# design.net
KiCad netlist of a schematic drawn in EasyEDA Pro
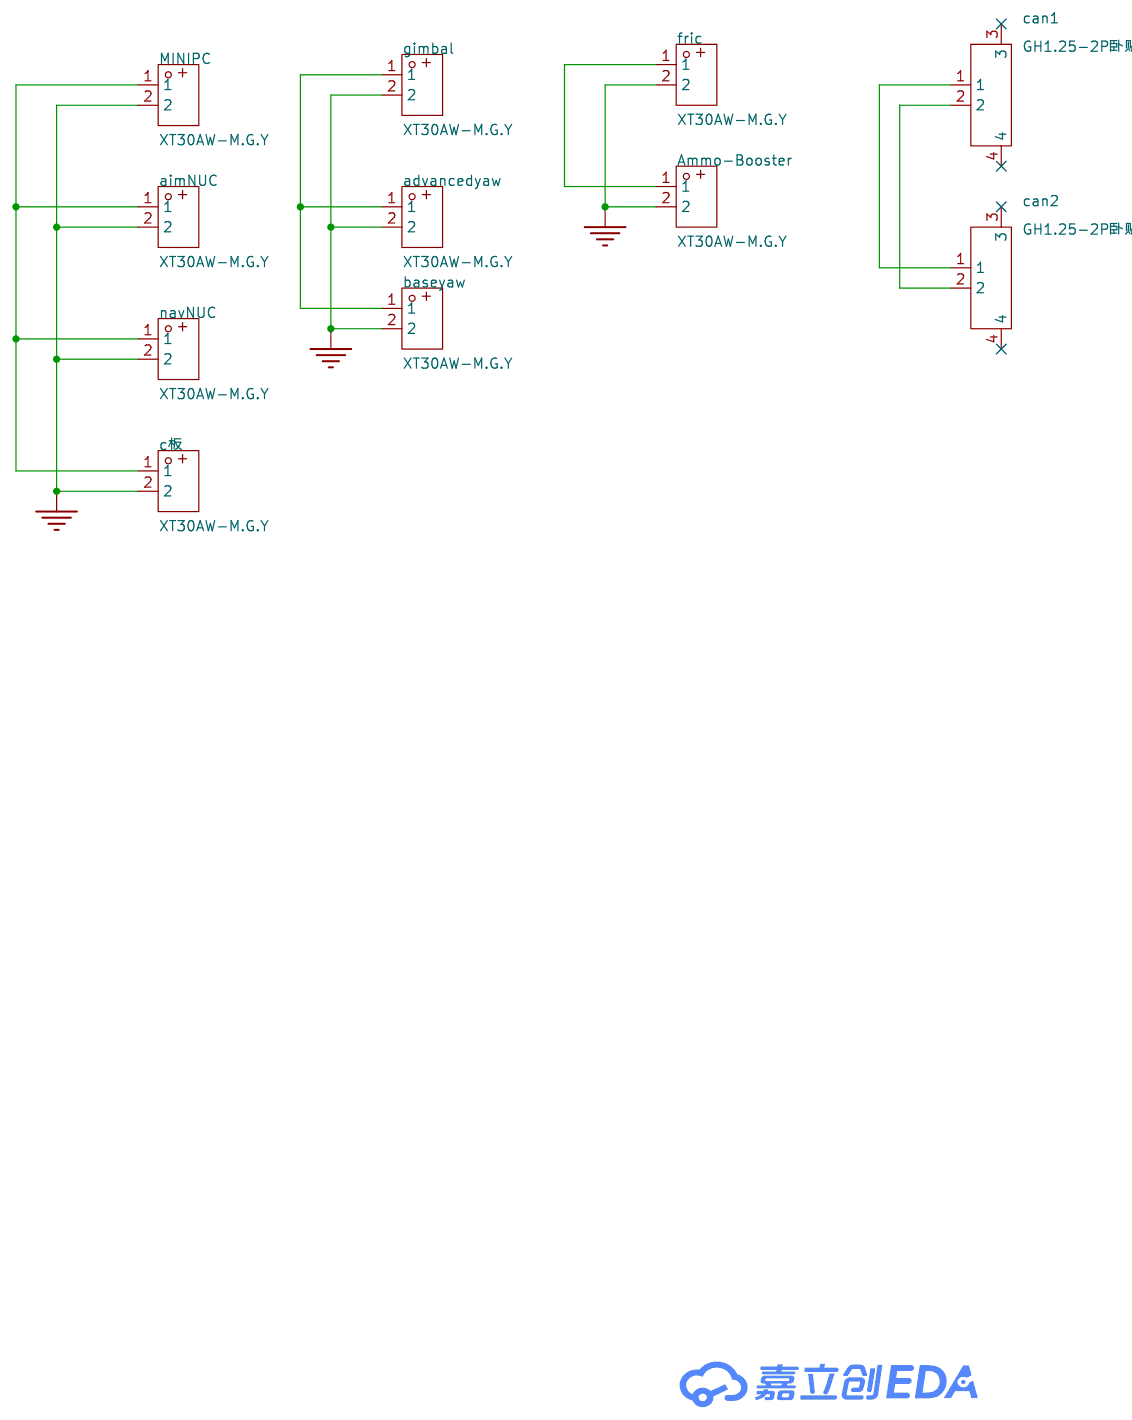
[diagram p0: schematic sheet]

(export (version "E")
  (design (tool "Eeschema 10.0.6"))
  (components
    (comp (ref "advancedyaw")
      (value "XT30AW-M.G.Y")
      (footprint "easyedapro:CONN-TH_XT30AW-M.G.Y")
      (fields (field (name "Manufacturer") "AMASS(艾迈斯)"))
      (libsource (lib "easyedapro") (part "XT30AW-M.G.Y"))
    )
    (comp (ref "aimNUC")
      (value "XT30AW-M.G.Y")
      (footprint "easyedapro:CONN-TH_XT30AW-M.G.Y")
      (fields (field (name "Manufacturer") "AMASS(艾迈斯)"))
      (libsource (lib "easyedapro") (part "XT30AW-M.G.Y"))
    )
    (comp (ref "Ammo-Booster")
      (value "XT30AW-M.G.Y")
      (footprint "easyedapro:CONN-TH_XT30AW-M.G.Y")
      (fields (field (name "Manufacturer") "AMASS(艾迈斯)"))
      (libsource (lib "easyedapro") (part "XT30AW-M.G.Y"))
    )
    (comp (ref "baseyaw")
      (value "XT30AW-M.G.Y")
      (footprint "easyedapro:CONN-TH_XT30AW-M.G.Y")
      (fields (field (name "Manufacturer") "AMASS(艾迈斯)"))
      (libsource (lib "easyedapro") (part "XT30AW-M.G.Y"))
    )
    (comp (ref "can1")
      (value "GH1.25-2P卧贴")
      (footprint "easyedapro:CONN-SMD_2P-P1.25_X1251WRS-02HF-LPSW")
      (libsource (lib "easyedapro") (part "GH1.25-2P卧贴_C9900015099"))
    )
    (comp (ref "can2")
      (value "GH1.25-2P卧贴")
      (footprint "easyedapro:CONN-SMD_2P-P1.25_X1251WRS-02HF-LPSW")
      (libsource (lib "easyedapro") (part "GH1.25-2P卧贴_C9900015099"))
    )
    (comp (ref "c板")
      (value "XT30AW-M.G.Y")
      (footprint "easyedapro:CONN-TH_XT30AW-M.G.Y")
      (fields (field (name "Manufacturer") "AMASS(艾迈斯)"))
      (libsource (lib "easyedapro") (part "XT30AW-M.G.Y"))
    )
    (comp (ref "fric")
      (value "XT30AW-M.G.Y")
      (footprint "easyedapro:CONN-TH_XT30AW-M.G.Y")
      (fields (field (name "Manufacturer") "AMASS(艾迈斯)"))
      (libsource (lib "easyedapro") (part "XT30AW-M.G.Y"))
    )
    (comp (ref "gimbal")
      (value "XT30AW-M.G.Y")
      (footprint "easyedapro:CONN-TH_XT30AW-M.G.Y")
      (fields (field (name "Manufacturer") "AMASS(艾迈斯)"))
      (libsource (lib "easyedapro") (part "XT30AW-M.G.Y"))
    )
    (comp (ref "MINIPC")
      (value "XT30AW-M.G.Y")
      (footprint "easyedapro:CONN-TH_XT30AW-M.G.Y")
      (fields (field (name "Manufacturer") "AMASS(艾迈斯)"))
      (libsource (lib "easyedapro") (part "XT30AW-M.G.Y"))
    )
    (comp (ref "navNUC")
      (value "XT30AW-M.G.Y")
      (footprint "easyedapro:CONN-TH_XT30AW-M.G.Y")
      (fields (field (name "Manufacturer") "AMASS(艾迈斯)"))
      (libsource (lib "easyedapro") (part "XT30AW-M.G.Y"))
    )
  )
  (nets
    (net (code "1") (name "GND") (class "Default")
      (node (ref "Ammo-Booster") (pin "2") (pinfunction "2_2") (pintype "unspecified"))
      (node (ref "MINIPC") (pin "2") (pinfunction "2_2") (pintype "unspecified"))
      (node (ref "advancedyaw") (pin "2") (pinfunction "2_2") (pintype "unspecified"))
      (node (ref "aimNUC") (pin "2") (pinfunction "2_2") (pintype "unspecified"))
      (node (ref "baseyaw") (pin "2") (pinfunction "2_2") (pintype "unspecified"))
      (node (ref "c板") (pin "2") (pinfunction "2_2") (pintype "unspecified"))
      (node (ref "fric") (pin "2") (pinfunction "2_2") (pintype "unspecified"))
      (node (ref "gimbal") (pin "2") (pinfunction "2_2") (pintype "unspecified"))
      (node (ref "navNUC") (pin "2") (pinfunction "2_2") (pintype "unspecified"))
    )
    (net (code "2") (name "Net-(Ammo-Booster-Pad1)") (class "Default")
      (node (ref "Ammo-Booster") (pin "1") (pinfunction "1_1") (pintype "unspecified"))
      (node (ref "fric") (pin "1") (pinfunction "1_1") (pintype "unspecified"))
    )
    (net (code "3") (name "Net-(MINIPC-Pad1)") (class "Default")
      (node (ref "MINIPC") (pin "1") (pinfunction "1_1") (pintype "unspecified"))
      (node (ref "aimNUC") (pin "1") (pinfunction "1_1") (pintype "unspecified"))
      (node (ref "c板") (pin "1") (pinfunction "1_1") (pintype "unspecified"))
      (node (ref "navNUC") (pin "1") (pinfunction "1_1") (pintype "unspecified"))
    )
    (net (code "4") (name "Net-(advancedyaw-Pad1)") (class "Default")
      (node (ref "advancedyaw") (pin "1") (pinfunction "1_1") (pintype "unspecified"))
      (node (ref "baseyaw") (pin "1") (pinfunction "1_1") (pintype "unspecified"))
      (node (ref "gimbal") (pin "1") (pinfunction "1_1") (pintype "unspecified"))
    )
    (net (code "5") (name "Net-(can1-Pad1)") (class "Default")
      (node (ref "can1") (pin "1") (pinfunction "1_1") (pintype "unspecified"))
      (node (ref "can2") (pin "1") (pinfunction "1_1") (pintype "unspecified"))
    )
    (net (code "6") (name "Net-(can1-Pad2)") (class "Default")
      (node (ref "can1") (pin "2") (pinfunction "2_2") (pintype "unspecified"))
      (node (ref "can2") (pin "2") (pinfunction "2_2") (pintype "unspecified"))
    )
    (net (code "7") (name "unconnected-(can1-Pad3)") (class "Default")
      (node (ref "can1") (pin "3") (pinfunction "3_3") (pintype "unspecified+no_connect"))
    )
    (net (code "8") (name "unconnected-(can1-Pad4)") (class "Default")
      (node (ref "can1") (pin "4") (pinfunction "4_4") (pintype "unspecified+no_connect"))
    )
    (net (code "9") (name "unconnected-(can2-Pad3)") (class "Default")
      (node (ref "can2") (pin "3") (pinfunction "3_3") (pintype "unspecified+no_connect"))
    )
    (net (code "10") (name "unconnected-(can2-Pad4)") (class "Default")
      (node (ref "can2") (pin "4") (pinfunction "4_4") (pintype "unspecified+no_connect"))
    )
  )
)
